# arduino_uno_shield.net
KiCad netlist of a schematic drawn in EAGLE
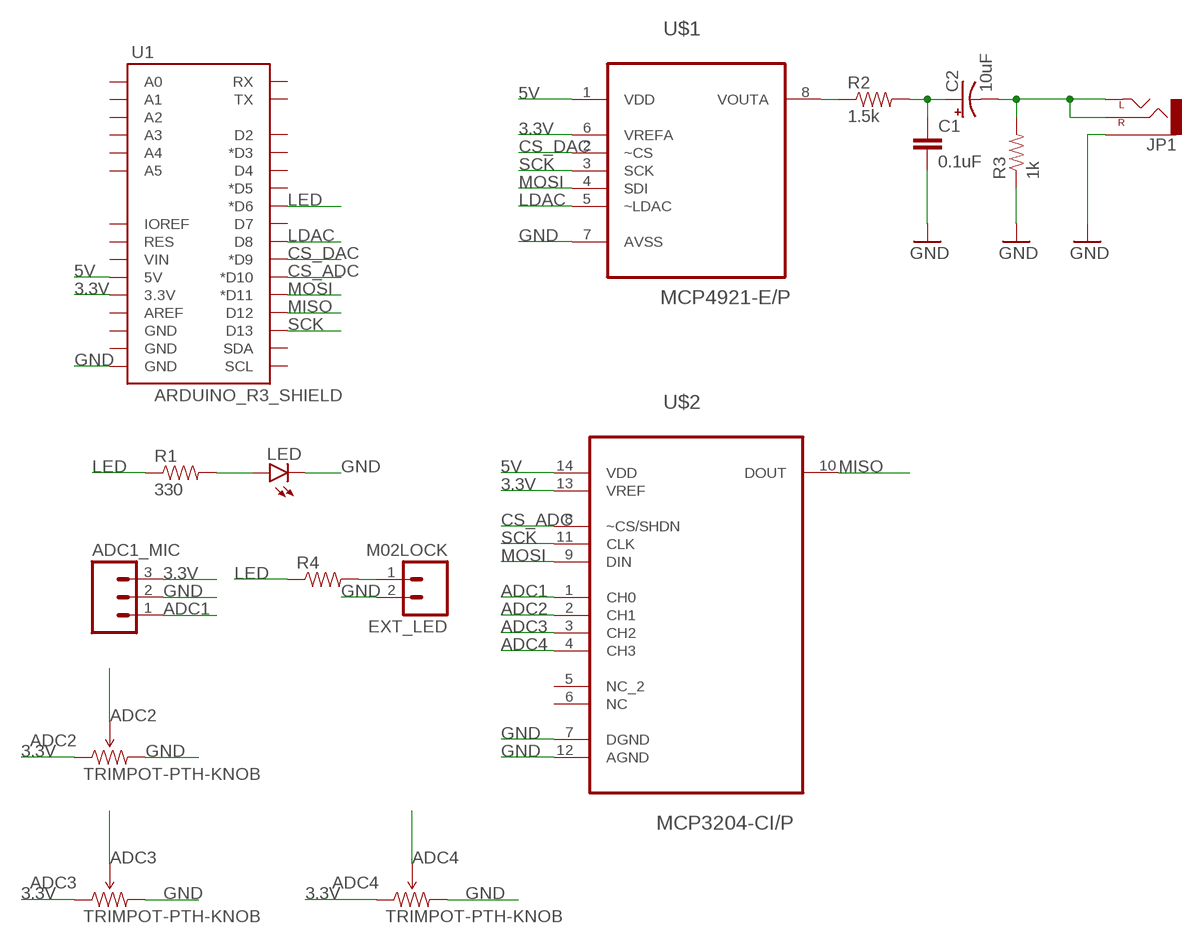
[diagram p0: schematic, sheet 1]

(export (version "E")
  (design (tool "Eeschema 10.0.6"))
  (components
    (comp (ref "ADC1_MIC")
      (value "M03LOCK")
      (footprint "eagle-import:1X03_LOCK")
      (libsource (lib "eagle-import") (part "M03LOCK"))
    )
    (comp (ref "ADC2")
      (value "TRIMPOT-PTH-KNOB")
      (footprint "eagle-import:3386U")
      (libsource (lib "eagle-import") (part "TRIMPOT-PTH-KNOB"))
    )
    (comp (ref "ADC3")
      (value "TRIMPOT-PTH-KNOB")
      (footprint "eagle-import:3386U")
      (libsource (lib "eagle-import") (part "TRIMPOT-PTH-KNOB"))
    )
    (comp (ref "ADC4")
      (value "TRIMPOT-PTH-KNOB")
      (footprint "eagle-import:3386U")
      (libsource (lib "eagle-import") (part "TRIMPOT-PTH-KNOB"))
    )
    (comp (ref "C1")
      (value "0.1uF")
      (footprint "eagle-import:CAP-PTH-5MM")
      (libsource (lib "eagle-import") (part "CAPPTH1"))
    )
    (comp (ref "C2")
      (value "10uF")
      (footprint "eagle-import:CPOL-RADIAL-10UF-25V")
      (libsource (lib "eagle-import") (part "CAP_POLPTH2"))
    )
    (comp (ref "EXT_LED")
      (value "M02LOCK")
      (footprint "eagle-import:1X02_LOCK")
      (libsource (lib "eagle-import") (part "M02LOCK"))
    )
    (comp (ref "JP1")
      (value "AUDIO-JACKPTH")
      (footprint "eagle-import:AUDIO-JACK")
      (libsource (lib "eagle-import") (part "AUDIO-JACKPTH"))
    )
    (comp (ref "LED")
      (value "LED5MM")
      (footprint "eagle-import:LED5MM")
      (libsource (lib "eagle-import") (part "LED5MM"))
    )
    (comp (ref "R1")
      (value "330")
      (footprint "eagle-import:AXIAL-0.4")
      (libsource (lib "eagle-import") (part "RESISTORPTH-1/4W"))
    )
    (comp (ref "R2")
      (value "1.5k")
      (footprint "eagle-import:AXIAL-0.4")
      (libsource (lib "eagle-import") (part "RESISTORPTH-1/4W"))
    )
    (comp (ref "R3")
      (value "1k")
      (footprint "eagle-import:AXIAL-0.4")
      (libsource (lib "eagle-import") (part "RESISTORPTH-1/4W"))
    )
    (comp (ref "R4")
      (value "RESISTORPTH-1/4W")
      (footprint "eagle-import:AXIAL-0.4")
      (libsource (lib "eagle-import") (part "RESISTORPTH-1/4W"))
    )
    (comp (ref "U$1")
      (value "MCP4921-E/P")
      (footprint "eagle-import:DIP254P762X432-8")
      (libsource (lib "eagle-import") (part "MCP4921-E/P"))
    )
    (comp (ref "U$2")
      (value "MCP3204-CI/P")
      (footprint "eagle-import:DIP254P762X432-14")
      (libsource (lib "eagle-import") (part "MCP3204-CI/P"))
    )
    (comp (ref "U1")
      (value "ARDUINO_R3_SHIELD")
      (footprint "eagle-import:UNO_R3_SHIELD")
      (libsource (lib "eagle-import") (part "ARDUINO_R3_SHIELD"))
    )
  )
  (nets
    (net (code "1") (name "/3.3V") (class "Default")
      (node (ref "ADC1_MIC") (pin "3") (pinfunction "3_3") (pintype "passive"))
      (node (ref "ADC2") (pin "1") (pinfunction "CCW_1") (pintype "passive"))
      (node (ref "ADC3") (pin "1") (pinfunction "CCW_1") (pintype "passive"))
      (node (ref "ADC4") (pin "1") (pinfunction "CCW_1") (pintype "passive"))
      (node (ref "U$1") (pin "6") (pinfunction "VREFA_6") (pintype "input"))
      (node (ref "U$2") (pin "13") (pinfunction "VREF_13") (pintype "power_in"))
      (node (ref "U1") (pin "3.3V") (pinfunction "3.3V_3.3V") (pintype "bidirectional"))
    )
    (net (code "2") (name "/5V") (class "Default")
      (node (ref "U$1") (pin "1") (pinfunction "VDD_1") (pintype "power_in"))
      (node (ref "U$2") (pin "14") (pinfunction "VDD_14") (pintype "power_in"))
      (node (ref "U1") (pin "5V") (pinfunction "5V_5V") (pintype "bidirectional"))
    )
    (net (code "3") (name "/ADC1") (class "Default")
      (node (ref "ADC1_MIC") (pin "1") (pinfunction "1_1") (pintype "passive"))
      (node (ref "U$2") (pin "1") (pinfunction "CH0_1") (pintype "input"))
    )
    (net (code "4") (name "/ADC2") (class "Default")
      (node (ref "ADC2") (pin "2") (pinfunction "WIPER_2") (pintype "passive"))
      (node (ref "U$2") (pin "2") (pinfunction "CH1_2") (pintype "input"))
    )
    (net (code "5") (name "/ADC3") (class "Default")
      (node (ref "ADC3") (pin "2") (pinfunction "WIPER_2") (pintype "passive"))
      (node (ref "U$2") (pin "3") (pinfunction "CH2_3") (pintype "input"))
    )
    (net (code "6") (name "/ADC4") (class "Default")
      (node (ref "ADC4") (pin "2") (pinfunction "WIPER_2") (pintype "passive"))
      (node (ref "U$2") (pin "4") (pinfunction "CH3_4") (pintype "input"))
    )
    (net (code "7") (name "/CS_ADC") (class "Default")
      (node (ref "U$2") (pin "8") (pinfunction "~{CS/SHDN}_8") (pintype "input"))
      (node (ref "U1") (pin "D10") (pinfunction "*D10_D10") (pintype "bidirectional"))
    )
    (net (code "8") (name "/CS_DAC") (class "Default")
      (node (ref "U$1") (pin "2") (pinfunction "~{CS}_2") (pintype "input"))
      (node (ref "U1") (pin "D9") (pinfunction "*D9_D9") (pintype "bidirectional"))
    )
    (net (code "9") (name "/LDAC") (class "Default")
      (node (ref "U$1") (pin "5") (pinfunction "~{LDAC}_5") (pintype "input"))
      (node (ref "U1") (pin "D8") (pinfunction "D8_D8") (pintype "bidirectional"))
    )
    (net (code "10") (name "/LED") (class "Default")
      (node (ref "R1") (pin "P$1") (pinfunction "1_P$1") (pintype "passive"))
      (node (ref "R4") (pin "P$1") (pinfunction "1_P$1") (pintype "passive"))
      (node (ref "U1") (pin "D6") (pinfunction "*D6_D6") (pintype "bidirectional"))
    )
    (net (code "11") (name "/MISO") (class "Default")
      (node (ref "U$2") (pin "10") (pinfunction "DOUT_10") (pintype "output"))
      (node (ref "U1") (pin "D12") (pinfunction "D12_D12") (pintype "bidirectional"))
    )
    (net (code "12") (name "/MOSI") (class "Default")
      (node (ref "U$1") (pin "4") (pinfunction "SDI_4") (pintype "input"))
      (node (ref "U$2") (pin "9") (pinfunction "DIN_9") (pintype "input"))
      (node (ref "U1") (pin "D11") (pinfunction "*D11_D11") (pintype "bidirectional"))
    )
    (net (code "13") (name "/SCK") (class "Default")
      (node (ref "U$1") (pin "3") (pinfunction "SCK_3") (pintype "input"))
      (node (ref "U$2") (pin "11") (pinfunction "CLK_11") (pintype "input"))
      (node (ref "U1") (pin "D13") (pinfunction "D13_D13") (pintype "bidirectional"))
    )
    (net (code "14") (name "GND") (class "Default")
      (node (ref "ADC1_MIC") (pin "2") (pinfunction "2_2") (pintype "passive"))
      (node (ref "ADC2") (pin "3") (pinfunction "CW_3") (pintype "passive"))
      (node (ref "ADC3") (pin "3") (pinfunction "CW_3") (pintype "passive"))
      (node (ref "ADC4") (pin "3") (pinfunction "CW_3") (pintype "passive"))
      (node (ref "C1") (pin "2") (pinfunction "2_2") (pintype "passive"))
      (node (ref "EXT_LED") (pin "2") (pinfunction "2_2") (pintype "passive"))
      (node (ref "JP1") (pin "SLEEVE") (pinfunction "SLEEVE_SLEEVE") (pintype "bidirectional"))
      (node (ref "LED") (pin "K") (pinfunction "C_K") (pintype "passive"))
      (node (ref "R3") (pin "P$1") (pinfunction "1_P$1") (pintype "passive"))
      (node (ref "U$1") (pin "7") (pinfunction "AVSS_7") (pintype "passive"))
      (node (ref "U$2") (pin "12") (pinfunction "AGND_12") (pintype "passive"))
      (node (ref "U$2") (pin "7") (pinfunction "DGND_7") (pintype "passive"))
      (node (ref "U1") (pin "GND@0") (pinfunction "GND_GND@0") (pintype "bidirectional"))
    )
    (net (code "15") (name "Net-(C2-+)") (class "Default")
      (node (ref "C1") (pin "1") (pinfunction "1_1") (pintype "passive"))
      (node (ref "C2") (pin "1") (pinfunction "+_1") (pintype "passive"))
      (node (ref "R2") (pin "P$2") (pinfunction "2_P$2") (pintype "passive"))
    )
    (net (code "16") (name "Net-(C2--)") (class "Default")
      (node (ref "C2") (pin "2") (pinfunction "-_2") (pintype "passive"))
      (node (ref "JP1") (pin "RING") (pinfunction "RIGHT_RING") (pintype "bidirectional"))
      (node (ref "JP1") (pin "TIP") (pinfunction "LEFT_TIP") (pintype "bidirectional"))
      (node (ref "R3") (pin "P$2") (pinfunction "2_P$2") (pintype "passive"))
    )
    (net (code "17") (name "Net-(R1-2)") (class "Default")
      (node (ref "LED") (pin "A") (pinfunction "A_A") (pintype "passive"))
      (node (ref "R1") (pin "P$2") (pinfunction "2_P$2") (pintype "passive"))
    )
    (net (code "18") (name "Net-(R2-1)") (class "Default")
      (node (ref "R2") (pin "P$1") (pinfunction "1_P$1") (pintype "passive"))
      (node (ref "U$1") (pin "8") (pinfunction "VOUTA_8") (pintype "output"))
    )
    (net (code "19") (name "Net-(R4-2)") (class "Default")
      (node (ref "EXT_LED") (pin "1") (pinfunction "1_1") (pintype "passive"))
      (node (ref "R4") (pin "P$2") (pinfunction "2_P$2") (pintype "passive"))
    )
    (net (code "20") (name "unconnected-(U$2-NC-Pad6)") (class "Default")
      (node (ref "U$2") (pin "6") (pinfunction "NC_6") (pintype "no_connect"))
    )
    (net (code "21") (name "unconnected-(U$2-NC_2-Pad5)") (class "Default")
      (node (ref "U$2") (pin "5") (pinfunction "NC_2_5") (pintype "no_connect"))
    )
    (net (code "22") (name "unconnected-(U1-*D3-PadD3)") (class "Default")
      (node (ref "U1") (pin "D3") (pinfunction "*D3_D3") (pintype "bidirectional"))
    )
    (net (code "23") (name "unconnected-(U1-*D5-PadD5)") (class "Default")
      (node (ref "U1") (pin "D5") (pinfunction "*D5_D5") (pintype "bidirectional"))
    )
    (net (code "24") (name "unconnected-(U1-GND-PadGND@1)") (class "Default")
      (node (ref "U1") (pin "GND@1") (pinfunction "GND_GND@1") (pintype "bidirectional"))
    )
    (net (code "25") (name "unconnected-(U1-GND-PadGND@2)") (class "Default")
      (node (ref "U1") (pin "GND@2") (pinfunction "GND_GND@2") (pintype "bidirectional"))
    )
    (net (code "26") (name "unconnected-(U1-PadA0)") (class "Default")
      (node (ref "U1") (pin "A0") (pinfunction "A0_A0") (pintype "bidirectional"))
    )
    (net (code "27") (name "unconnected-(U1-PadA1)") (class "Default")
      (node (ref "U1") (pin "A1") (pinfunction "A1_A1") (pintype "bidirectional"))
    )
    (net (code "28") (name "unconnected-(U1-PadA2)") (class "Default")
      (node (ref "U1") (pin "A2") (pinfunction "A2_A2") (pintype "bidirectional"))
    )
    (net (code "29") (name "unconnected-(U1-PadA3)") (class "Default")
      (node (ref "U1") (pin "A3") (pinfunction "A3_A3") (pintype "bidirectional"))
    )
    (net (code "30") (name "unconnected-(U1-PadA4)") (class "Default")
      (node (ref "U1") (pin "A4") (pinfunction "A4_A4") (pintype "bidirectional"))
    )
    (net (code "31") (name "unconnected-(U1-PadA5)") (class "Default")
      (node (ref "U1") (pin "A5") (pinfunction "A5_A5") (pintype "bidirectional"))
    )
    (net (code "32") (name "unconnected-(U1-PadAREF)") (class "Default")
      (node (ref "U1") (pin "AREF") (pinfunction "AREF_AREF") (pintype "bidirectional"))
    )
    (net (code "33") (name "unconnected-(U1-PadD2)") (class "Default")
      (node (ref "U1") (pin "D2") (pinfunction "D2_D2") (pintype "bidirectional"))
    )
    (net (code "34") (name "unconnected-(U1-PadD4)") (class "Default")
      (node (ref "U1") (pin "D4") (pinfunction "D4_D4") (pintype "bidirectional"))
    )
    (net (code "35") (name "unconnected-(U1-PadD7)") (class "Default")
      (node (ref "U1") (pin "D7") (pinfunction "D7_D7") (pintype "bidirectional"))
    )
    (net (code "36") (name "unconnected-(U1-PadIOREF)") (class "Default")
      (node (ref "U1") (pin "IOREF") (pinfunction "IOREF_IOREF") (pintype "bidirectional"))
    )
    (net (code "37") (name "unconnected-(U1-PadRES)") (class "Default")
      (node (ref "U1") (pin "RES") (pinfunction "RES_RES") (pintype "bidirectional"))
    )
    (net (code "38") (name "unconnected-(U1-PadRX)") (class "Default")
      (node (ref "U1") (pin "RX") (pinfunction "RX_RX") (pintype "bidirectional"))
    )
    (net (code "39") (name "unconnected-(U1-PadSCL)") (class "Default")
      (node (ref "U1") (pin "SCL") (pinfunction "SCL_SCL") (pintype "bidirectional"))
    )
    (net (code "40") (name "unconnected-(U1-PadSDA)") (class "Default")
      (node (ref "U1") (pin "SDA") (pinfunction "SDA_SDA") (pintype "bidirectional"))
    )
    (net (code "41") (name "unconnected-(U1-PadTX)") (class "Default")
      (node (ref "U1") (pin "TX") (pinfunction "TX_TX") (pintype "bidirectional"))
    )
    (net (code "42") (name "unconnected-(U1-PadVIN)") (class "Default")
      (node (ref "U1") (pin "VIN") (pinfunction "VIN_VIN") (pintype "bidirectional"))
    )
  )
)
